# MCU.net
KiCad netlist of a schematic drawn in EAGLE
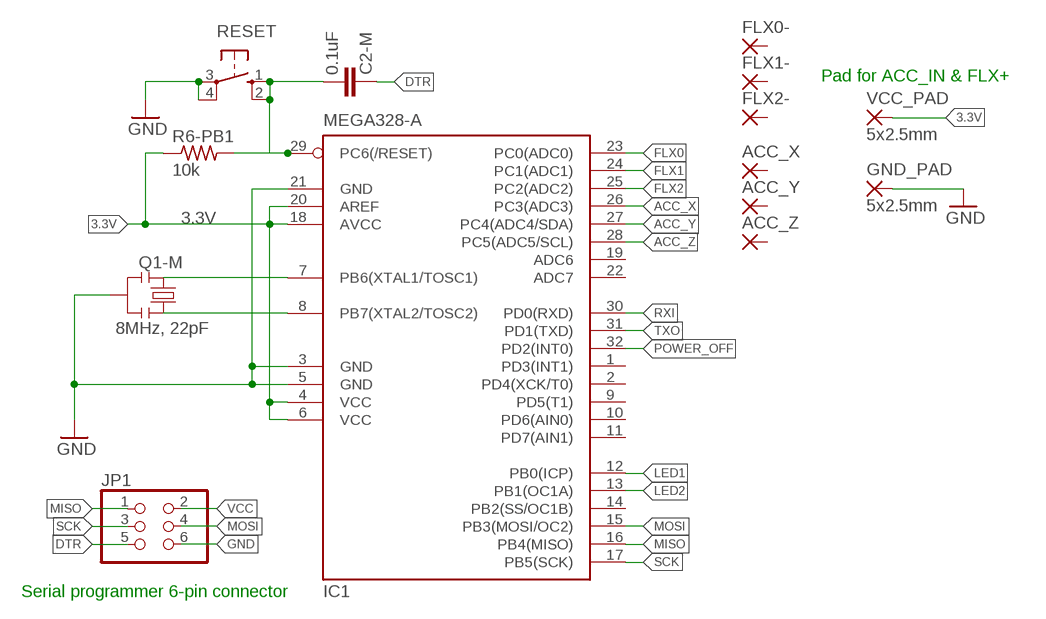
[diagram p0: schematic, sheet 1]

(export (version "E")
  (design (tool "Eeschema 10.0.6"))
  (components
    (comp (ref "ACC_X")
      (value "1,6/0,8")
      (footprint "eagle-import:1,6_0,8")
      (libsource (lib "eagle-import") (part "1,6/0,8"))
    )
    (comp (ref "ACC_Y")
      (value "1,6/0,8")
      (footprint "eagle-import:1,6_0,8")
      (libsource (lib "eagle-import") (part "1,6/0,8"))
    )
    (comp (ref "ACC_Z")
      (value "1,6/0,8")
      (footprint "eagle-import:1,6_0,8")
      (libsource (lib "eagle-import") (part "1,6/0,8"))
    )
    (comp (ref "C2-M")
      (value "0.1uF")
      (footprint "eagle-import:0603-CAP")
      (libsource (lib "eagle-import") (part "CAP0603-CAP"))
    )
    (comp (ref "FLX0-")
      (value "1,6/0,8")
      (footprint "eagle-import:1,6_0,8")
      (libsource (lib "eagle-import") (part "1,6/0,8"))
    )
    (comp (ref "FLX1-")
      (value "1,6/0,8")
      (footprint "eagle-import:1,6_0,8")
      (libsource (lib "eagle-import") (part "1,6/0,8"))
    )
    (comp (ref "FLX2-")
      (value "1,6/0,8")
      (footprint "eagle-import:1,6_0,8")
      (libsource (lib "eagle-import") (part "1,6/0,8"))
    )
    (comp (ref "GND_PAD")
      (value "5x2.5mm")
      (footprint "eagle-import:5-2,5")
      (libsource (lib "eagle-import") (part "WIREPADSMD5-2,5"))
    )
    (comp (ref "IC1")
      (value "MEGA328-A")
      (footprint "eagle-import:TQFP32-08")
      (fields (field (name "MPN") "ATMEGA8-16AU"))
      (libsource (lib "eagle-import") (part "MEGA8-AI"))
    )
    (comp (ref "JP1")
      (value "PINHD-2X3")
      (footprint "eagle-import:2X03")
      (libsource (lib "eagle-import") (part "PINHD-2X3"))
    )
    (comp (ref "Q1-M")
      (value "8MHz, 22pF")
      (footprint "eagle-import:RESONATOR-SMD-1_1")
      (libsource (lib "eagle-import") (part "RESONATOR1{colon}1"))
    )
    (comp (ref "R6-PB1")
      (value "10k")
      (footprint "eagle-import:R0805")
      (libsource (lib "eagle-import") (part "R-US_R0805"))
    )
    (comp (ref "RESET")
      (value "10-XX")
      (footprint "eagle-import:B3F-10XX")
      (fields (field (name "MPN") "B3F-1000"))
      (libsource (lib "eagle-import") (part "10-XX"))
    )
    (comp (ref "VCC_PAD")
      (value "5x2.5mm")
      (footprint "eagle-import:5-2,5")
      (libsource (lib "eagle-import") (part "WIREPADSMD5-2,5"))
    )
  )
  (nets
    (net (code "1") (name "3.3V") (class "Default")
      (node (ref "IC1") (pin "18") (pinfunction "AVCC_18") (pintype "power_in"))
      (node (ref "IC1") (pin "20") (pinfunction "AREF_20") (pintype "passive"))
      (node (ref "IC1") (pin "4") (pinfunction "VCC_4") (pintype "power_in"))
      (node (ref "IC1") (pin "6") (pinfunction "VCC_6") (pintype "power_in"))
      (node (ref "R6-PB1") (pin "1") (pinfunction "1_1") (pintype "passive"))
      (node (ref "VCC_PAD") (pin "1") (pinfunction "P_1") (pintype "passive"))
    )
    (net (code "2") (name "ACC_X") (class "Default")
      (node (ref "IC1") (pin "26") (pinfunction "PC3(ADC3)_26") (pintype "bidirectional"))
    )
    (net (code "3") (name "ACC_Y") (class "Default")
      (node (ref "IC1") (pin "27") (pinfunction "PC4(ADC4/SDA)_27") (pintype "bidirectional"))
    )
    (net (code "4") (name "ACC_Z") (class "Default")
      (node (ref "IC1") (pin "28") (pinfunction "PC5(ADC5/SCL)_28") (pintype "bidirectional"))
    )
    (net (code "5") (name "DTR") (class "Default")
      (node (ref "C2-M") (pin "2") (pinfunction "2_2") (pintype "passive"))
      (node (ref "JP1") (pin "5") (pinfunction "5_5") (pintype "passive"))
    )
    (net (code "6") (name "FLX0") (class "Default")
      (node (ref "IC1") (pin "23") (pinfunction "PC0(ADC0)_23") (pintype "bidirectional"))
    )
    (net (code "7") (name "FLX1") (class "Default")
      (node (ref "IC1") (pin "24") (pinfunction "PC1(ADC1)_24") (pintype "bidirectional"))
    )
    (net (code "8") (name "FLX2") (class "Default")
      (node (ref "IC1") (pin "25") (pinfunction "PC2(ADC2)_25") (pintype "bidirectional"))
    )
    (net (code "9") (name "GND") (class "Default")
      (node (ref "GND_PAD") (pin "1") (pinfunction "P_1") (pintype "passive"))
      (node (ref "IC1") (pin "21") (pinfunction "GND_21") (pintype "power_in"))
      (node (ref "IC1") (pin "3") (pinfunction "GND_3") (pintype "power_in"))
      (node (ref "IC1") (pin "5") (pinfunction "GND_5") (pintype "power_in"))
      (node (ref "JP1") (pin "6") (pinfunction "6_6") (pintype "passive"))
      (node (ref "Q1-M") (pin "2") (pinfunction "2_2") (pintype "passive"))
      (node (ref "RESET") (pin "3") (pinfunction "P_3") (pintype "passive"))
      (node (ref "RESET") (pin "4") (pinfunction "P1_4") (pintype "passive"))
    )
    (net (code "10") (name "LED1") (class "Default")
      (node (ref "IC1") (pin "12") (pinfunction "PB0(ICP)_12") (pintype "bidirectional"))
    )
    (net (code "11") (name "LED2") (class "Default")
      (node (ref "IC1") (pin "13") (pinfunction "PB1(OC1A)_13") (pintype "bidirectional"))
    )
    (net (code "12") (name "MISO") (class "Default")
      (node (ref "IC1") (pin "16") (pinfunction "PB4(MISO)_16") (pintype "bidirectional"))
      (node (ref "JP1") (pin "1") (pinfunction "1_1") (pintype "passive"))
    )
    (net (code "13") (name "MOSI") (class "Default")
      (node (ref "IC1") (pin "15") (pinfunction "PB3(MOSI/OC2)_15") (pintype "bidirectional"))
      (node (ref "JP1") (pin "4") (pinfunction "4_4") (pintype "passive"))
    )
    (net (code "14") (name "Net-(IC1-PB6(XTAL1{slash}TOSC1))") (class "Default")
      (node (ref "IC1") (pin "7") (pinfunction "PB6(XTAL1/TOSC1)_7") (pintype "bidirectional"))
      (node (ref "Q1-M") (pin "1") (pinfunction "1_1") (pintype "passive"))
    )
    (net (code "15") (name "Net-(IC1-PB7(XTAL2{slash}TOSC2))") (class "Default")
      (node (ref "IC1") (pin "8") (pinfunction "PB7(XTAL2/TOSC2)_8") (pintype "bidirectional"))
      (node (ref "Q1-M") (pin "3") (pinfunction "3_3") (pintype "passive"))
    )
    (net (code "16") (name "Net-(IC1-PC6({slash}RESET))") (class "Default")
      (node (ref "C2-M") (pin "1") (pinfunction "1_1") (pintype "passive"))
      (node (ref "IC1") (pin "29") (pinfunction "PC6(/RESET)_29") (pintype "bidirectional"))
      (node (ref "R6-PB1") (pin "2") (pinfunction "2_2") (pintype "passive"))
      (node (ref "RESET") (pin "1") (pinfunction "S_1") (pintype "passive"))
      (node (ref "RESET") (pin "2") (pinfunction "S1_2") (pintype "passive"))
    )
    (net (code "17") (name "POWER_OFF") (class "Default")
      (node (ref "IC1") (pin "32") (pinfunction "PD2(INT0)_32") (pintype "bidirectional"))
    )
    (net (code "18") (name "RXI") (class "Default")
      (node (ref "IC1") (pin "30") (pinfunction "PD0(RXD)_30") (pintype "bidirectional"))
    )
    (net (code "19") (name "SCK") (class "Default")
      (node (ref "IC1") (pin "17") (pinfunction "PB5(SCK)_17") (pintype "bidirectional"))
      (node (ref "JP1") (pin "3") (pinfunction "3_3") (pintype "passive"))
    )
    (net (code "20") (name "TXO") (class "Default")
      (node (ref "IC1") (pin "31") (pinfunction "PD1(TXD)_31") (pintype "bidirectional"))
    )
    (net (code "21") (name "VCC") (class "Default")
      (node (ref "JP1") (pin "2") (pinfunction "2_2") (pintype "passive"))
    )
    (net (code "22") (name "unconnected-(ACC_X-P-Pad1)") (class "Default")
      (node (ref "ACC_X") (pin "1") (pinfunction "P_1") (pintype "passive"))
    )
    (net (code "23") (name "unconnected-(ACC_Y-P-Pad1)") (class "Default")
      (node (ref "ACC_Y") (pin "1") (pinfunction "P_1") (pintype "passive"))
    )
    (net (code "24") (name "unconnected-(ACC_Z-P-Pad1)") (class "Default")
      (node (ref "ACC_Z") (pin "1") (pinfunction "P_1") (pintype "passive"))
    )
    (net (code "25") (name "unconnected-(FLX0--P-Pad1)") (class "Default")
      (node (ref "FLX0-") (pin "1") (pinfunction "P_1") (pintype "passive"))
    )
    (net (code "26") (name "unconnected-(FLX1--P-Pad1)") (class "Default")
      (node (ref "FLX1-") (pin "1") (pinfunction "P_1") (pintype "passive"))
    )
    (net (code "27") (name "unconnected-(FLX2--P-Pad1)") (class "Default")
      (node (ref "FLX2-") (pin "1") (pinfunction "P_1") (pintype "passive"))
    )
    (net (code "28") (name "unconnected-(IC1-ADC6-Pad19)") (class "Default")
      (node (ref "IC1") (pin "19") (pinfunction "ADC6_19") (pintype "bidirectional"))
    )
    (net (code "29") (name "unconnected-(IC1-ADC7-Pad22)") (class "Default")
      (node (ref "IC1") (pin "22") (pinfunction "ADC7_22") (pintype "bidirectional"))
    )
    (net (code "30") (name "unconnected-(IC1-PB2(SS{slash}OC1B)-Pad14)") (class "Default")
      (node (ref "IC1") (pin "14") (pinfunction "PB2(SS/OC1B)_14") (pintype "bidirectional"))
    )
    (net (code "31") (name "unconnected-(IC1-PD3(INT1)-Pad1)") (class "Default")
      (node (ref "IC1") (pin "1") (pinfunction "PD3(INT1)_1") (pintype "bidirectional"))
    )
    (net (code "32") (name "unconnected-(IC1-PD4(XCK{slash}T0)-Pad2)") (class "Default")
      (node (ref "IC1") (pin "2") (pinfunction "PD4(XCK/T0)_2") (pintype "bidirectional"))
    )
    (net (code "33") (name "unconnected-(IC1-PD5(T1)-Pad9)") (class "Default")
      (node (ref "IC1") (pin "9") (pinfunction "PD5(T1)_9") (pintype "bidirectional"))
    )
    (net (code "34") (name "unconnected-(IC1-PD6(AIN0)-Pad10)") (class "Default")
      (node (ref "IC1") (pin "10") (pinfunction "PD6(AIN0)_10") (pintype "bidirectional"))
    )
    (net (code "35") (name "unconnected-(IC1-PD7(AIN1)-Pad11)") (class "Default")
      (node (ref "IC1") (pin "11") (pinfunction "PD7(AIN1)_11") (pintype "bidirectional"))
    )
  )
)
